# control.net
KiCad netlist of a schematic drawn in EAGLE
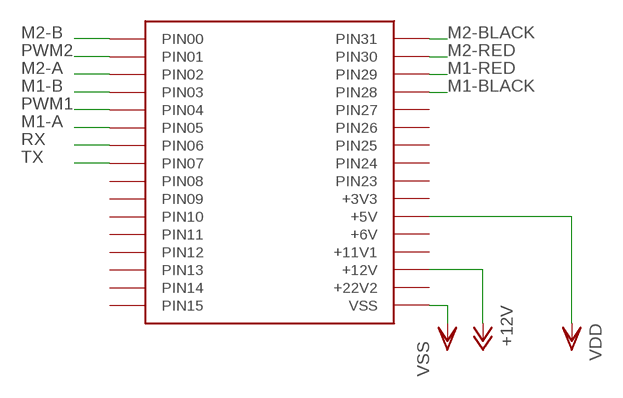
[diagram p0: schematic, sheet 1]
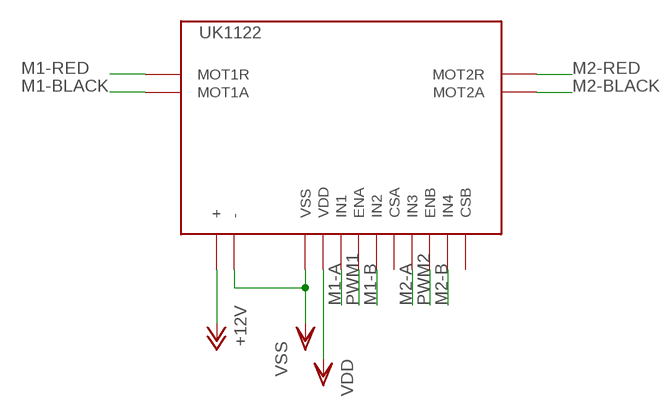
[diagram p1: schematic, sheet 2]
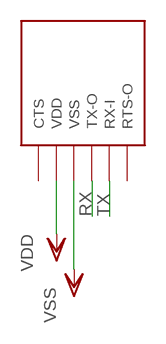
[diagram p2: schematic, sheet 3]

(export (version "E")
  (design (tool "Eeschema 10.0.6"))
  (components
    (comp (ref "U$1")
      (value "BASE")
      (footprint "eagle-import:BASE")
      (libsource (lib "eagle-import") (part "BASE"))
    )
    (comp (ref "U$3")
      (value "BLUESMIRF")
      (footprint "eagle-import:BLUESMIRF")
      (libsource (lib "eagle-import") (part "BLUESMIRF"))
    )
    (comp (ref "UK1122")
      (value "UK1122")
      (footprint "eagle-import:UK1122")
      (libsource (lib "eagle-import") (part "UK1122"))
    )
  )
  (nets
    (net (code "1") (name "+12V") (class "Default")
      (node (ref "U$1") (pin "PIN18") (pinfunction "+12V_PIN18") (pintype "bidirectional"))
      (node (ref "UK1122") (pin "+") (pinfunction "+_+") (pintype "power_in"))
    )
    (net (code "2") (name "M1-A") (class "Default")
      (node (ref "U$1") (pin "PIN05") (pinfunction "PIN05_PIN05") (pintype "bidirectional"))
      (node (ref "UK1122") (pin "IN1") (pinfunction "IN1_IN1") (pintype "input"))
    )
    (net (code "3") (name "M1-B") (class "Default")
      (node (ref "U$1") (pin "PIN03") (pinfunction "PIN03_PIN03") (pintype "bidirectional"))
      (node (ref "UK1122") (pin "EN2") (pinfunction "IN2_EN2") (pintype "input"))
    )
    (net (code "4") (name "M1-BLACK") (class "Default")
      (node (ref "U$1") (pin "PIN28") (pinfunction "PIN28_PIN28") (pintype "bidirectional"))
      (node (ref "UK1122") (pin "MOT1A") (pinfunction "MOT1A_MOT1A") (pintype "bidirectional"))
    )
    (net (code "5") (name "M1-RED") (class "Default")
      (node (ref "U$1") (pin "PIN29") (pinfunction "PIN29_PIN29") (pintype "bidirectional"))
      (node (ref "UK1122") (pin "MOT1R") (pinfunction "MOT1R_MOT1R") (pintype "bidirectional"))
    )
    (net (code "6") (name "M2-A") (class "Default")
      (node (ref "U$1") (pin "PIN02") (pinfunction "PIN02_PIN02") (pintype "bidirectional"))
      (node (ref "UK1122") (pin "IN3") (pinfunction "IN3_IN3") (pintype "input"))
    )
    (net (code "7") (name "M2-B") (class "Default")
      (node (ref "U$1") (pin "PIN00") (pinfunction "PIN00_PIN00") (pintype "bidirectional"))
      (node (ref "UK1122") (pin "IN4") (pinfunction "IN4_IN4") (pintype "input"))
    )
    (net (code "8") (name "M2-BLACK") (class "Default")
      (node (ref "U$1") (pin "PIN31") (pinfunction "PIN31_PIN31") (pintype "bidirectional"))
      (node (ref "UK1122") (pin "MOT2A") (pinfunction "MOT2A_MOT2A") (pintype "bidirectional"))
    )
    (net (code "9") (name "M2-RED") (class "Default")
      (node (ref "U$1") (pin "PIN30") (pinfunction "PIN30_PIN30") (pintype "bidirectional"))
      (node (ref "UK1122") (pin "MOT2R") (pinfunction "MOT2R_MOT2R") (pintype "bidirectional"))
    )
    (net (code "10") (name "PWM1") (class "Default")
      (node (ref "U$1") (pin "PIN04") (pinfunction "PIN04_PIN04") (pintype "bidirectional"))
      (node (ref "UK1122") (pin "ENA") (pinfunction "ENA_ENA") (pintype "input"))
    )
    (net (code "11") (name "PWM2") (class "Default")
      (node (ref "U$1") (pin "PIN01") (pinfunction "PIN01_PIN01") (pintype "bidirectional"))
      (node (ref "UK1122") (pin "ENB") (pinfunction "ENB_ENB") (pintype "bidirectional"))
    )
    (net (code "12") (name "RX") (class "Default")
      (node (ref "U$1") (pin "PIN06") (pinfunction "PIN06_PIN06") (pintype "bidirectional"))
      (node (ref "U$3") (pin "TX-O") (pinfunction "TX-O_TX-O") (pintype "output"))
    )
    (net (code "13") (name "TX") (class "Default")
      (node (ref "U$1") (pin "PIN07") (pinfunction "PIN07_PIN07") (pintype "bidirectional"))
      (node (ref "U$3") (pin "RX-I") (pinfunction "RX-I_RX-I") (pintype "input"))
    )
    (net (code "14") (name "VDD") (class "Default")
      (node (ref "U$1") (pin "PIN21") (pinfunction "+5V_PIN21") (pintype "bidirectional"))
      (node (ref "U$3") (pin "VDD") (pinfunction "VDD_VDD") (pintype "power_in"))
      (node (ref "UK1122") (pin "+5") (pinfunction "VDD_+5") (pintype "power_in"))
    )
    (net (code "15") (name "VSS") (class "Default")
      (node (ref "U$1") (pin "PIN16") (pinfunction "VSS_PIN16") (pintype "bidirectional"))
      (node (ref "U$3") (pin "VSS") (pinfunction "VSS_VSS") (pintype "power_in"))
      (node (ref "UK1122") (pin "-") (pinfunction "-_-") (pintype "power_in"))
      (node (ref "UK1122") (pin "GND") (pinfunction "VSS_GND") (pintype "power_in"))
    )
    (net (code "16") (name "unconnected-(U$1-+3V3-PadPIN22)") (class "Default")
      (node (ref "U$1") (pin "PIN22") (pinfunction "+3V3_PIN22") (pintype "bidirectional"))
    )
    (net (code "17") (name "unconnected-(U$1-+6V-PadPIN20)") (class "Default")
      (node (ref "U$1") (pin "PIN20") (pinfunction "+6V_PIN20") (pintype "bidirectional"))
    )
    (net (code "18") (name "unconnected-(U$1-+11V1-PadPIN19)") (class "Default")
      (node (ref "U$1") (pin "PIN19") (pinfunction "+11V1_PIN19") (pintype "bidirectional"))
    )
    (net (code "19") (name "unconnected-(U$1-+22V2-PadPIN17)") (class "Default")
      (node (ref "U$1") (pin "PIN17") (pinfunction "+22V2_PIN17") (pintype "bidirectional"))
    )
    (net (code "20") (name "unconnected-(U$1-PadPIN08)") (class "Default")
      (node (ref "U$1") (pin "PIN08") (pinfunction "PIN08_PIN08") (pintype "bidirectional"))
    )
    (net (code "21") (name "unconnected-(U$1-PadPIN09)") (class "Default")
      (node (ref "U$1") (pin "PIN09") (pinfunction "PIN09_PIN09") (pintype "bidirectional"))
    )
    (net (code "22") (name "unconnected-(U$1-PadPIN10)") (class "Default")
      (node (ref "U$1") (pin "PIN10") (pinfunction "PIN10_PIN10") (pintype "bidirectional"))
    )
    (net (code "23") (name "unconnected-(U$1-PadPIN11)") (class "Default")
      (node (ref "U$1") (pin "PIN11") (pinfunction "PIN11_PIN11") (pintype "bidirectional"))
    )
    (net (code "24") (name "unconnected-(U$1-PadPIN12)") (class "Default")
      (node (ref "U$1") (pin "PIN12") (pinfunction "PIN12_PIN12") (pintype "bidirectional"))
    )
    (net (code "25") (name "unconnected-(U$1-PadPIN13)") (class "Default")
      (node (ref "U$1") (pin "PIN13") (pinfunction "PIN13_PIN13") (pintype "bidirectional"))
    )
    (net (code "26") (name "unconnected-(U$1-PadPIN14)") (class "Default")
      (node (ref "U$1") (pin "PIN14") (pinfunction "PIN14_PIN14") (pintype "bidirectional"))
    )
    (net (code "27") (name "unconnected-(U$1-PadPIN15)") (class "Default")
      (node (ref "U$1") (pin "PIN15") (pinfunction "PIN15_PIN15") (pintype "bidirectional"))
    )
    (net (code "28") (name "unconnected-(U$1-PadPIN23)") (class "Default")
      (node (ref "U$1") (pin "PIN23") (pinfunction "PIN23_PIN23") (pintype "bidirectional"))
    )
    (net (code "29") (name "unconnected-(U$1-PadPIN24)") (class "Default")
      (node (ref "U$1") (pin "PIN24") (pinfunction "PIN24_PIN24") (pintype "bidirectional"))
    )
    (net (code "30") (name "unconnected-(U$1-PadPIN25)") (class "Default")
      (node (ref "U$1") (pin "PIN25") (pinfunction "PIN25_PIN25") (pintype "bidirectional"))
    )
    (net (code "31") (name "unconnected-(U$1-PadPIN26)") (class "Default")
      (node (ref "U$1") (pin "PIN26") (pinfunction "PIN26_PIN26") (pintype "bidirectional"))
    )
    (net (code "32") (name "unconnected-(U$1-PadPIN27)") (class "Default")
      (node (ref "U$1") (pin "PIN27") (pinfunction "PIN27_PIN27") (pintype "bidirectional"))
    )
    (net (code "33") (name "unconnected-(U$3-CTS-PadCTS-I)") (class "Default")
      (node (ref "U$3") (pin "CTS-I") (pinfunction "CTS_CTS-I") (pintype "input"))
    )
    (net (code "34") (name "unconnected-(U$3-PadRTS-O)") (class "Default")
      (node (ref "U$3") (pin "RTS-O") (pinfunction "RTS-O_RTS-O") (pintype "output"))
    )
    (net (code "35") (name "unconnected-(UK1122-PadCSA)") (class "Default")
      (node (ref "UK1122") (pin "CSA") (pinfunction "CSA_CSA") (pintype "bidirectional"))
    )
    (net (code "36") (name "unconnected-(UK1122-PadCSB)") (class "Default")
      (node (ref "UK1122") (pin "CSB") (pinfunction "CSB_CSB") (pintype "bidirectional"))
    )
  )
)
